# Bubba.net
KiCad netlist of a schematic drawn in EAGLE
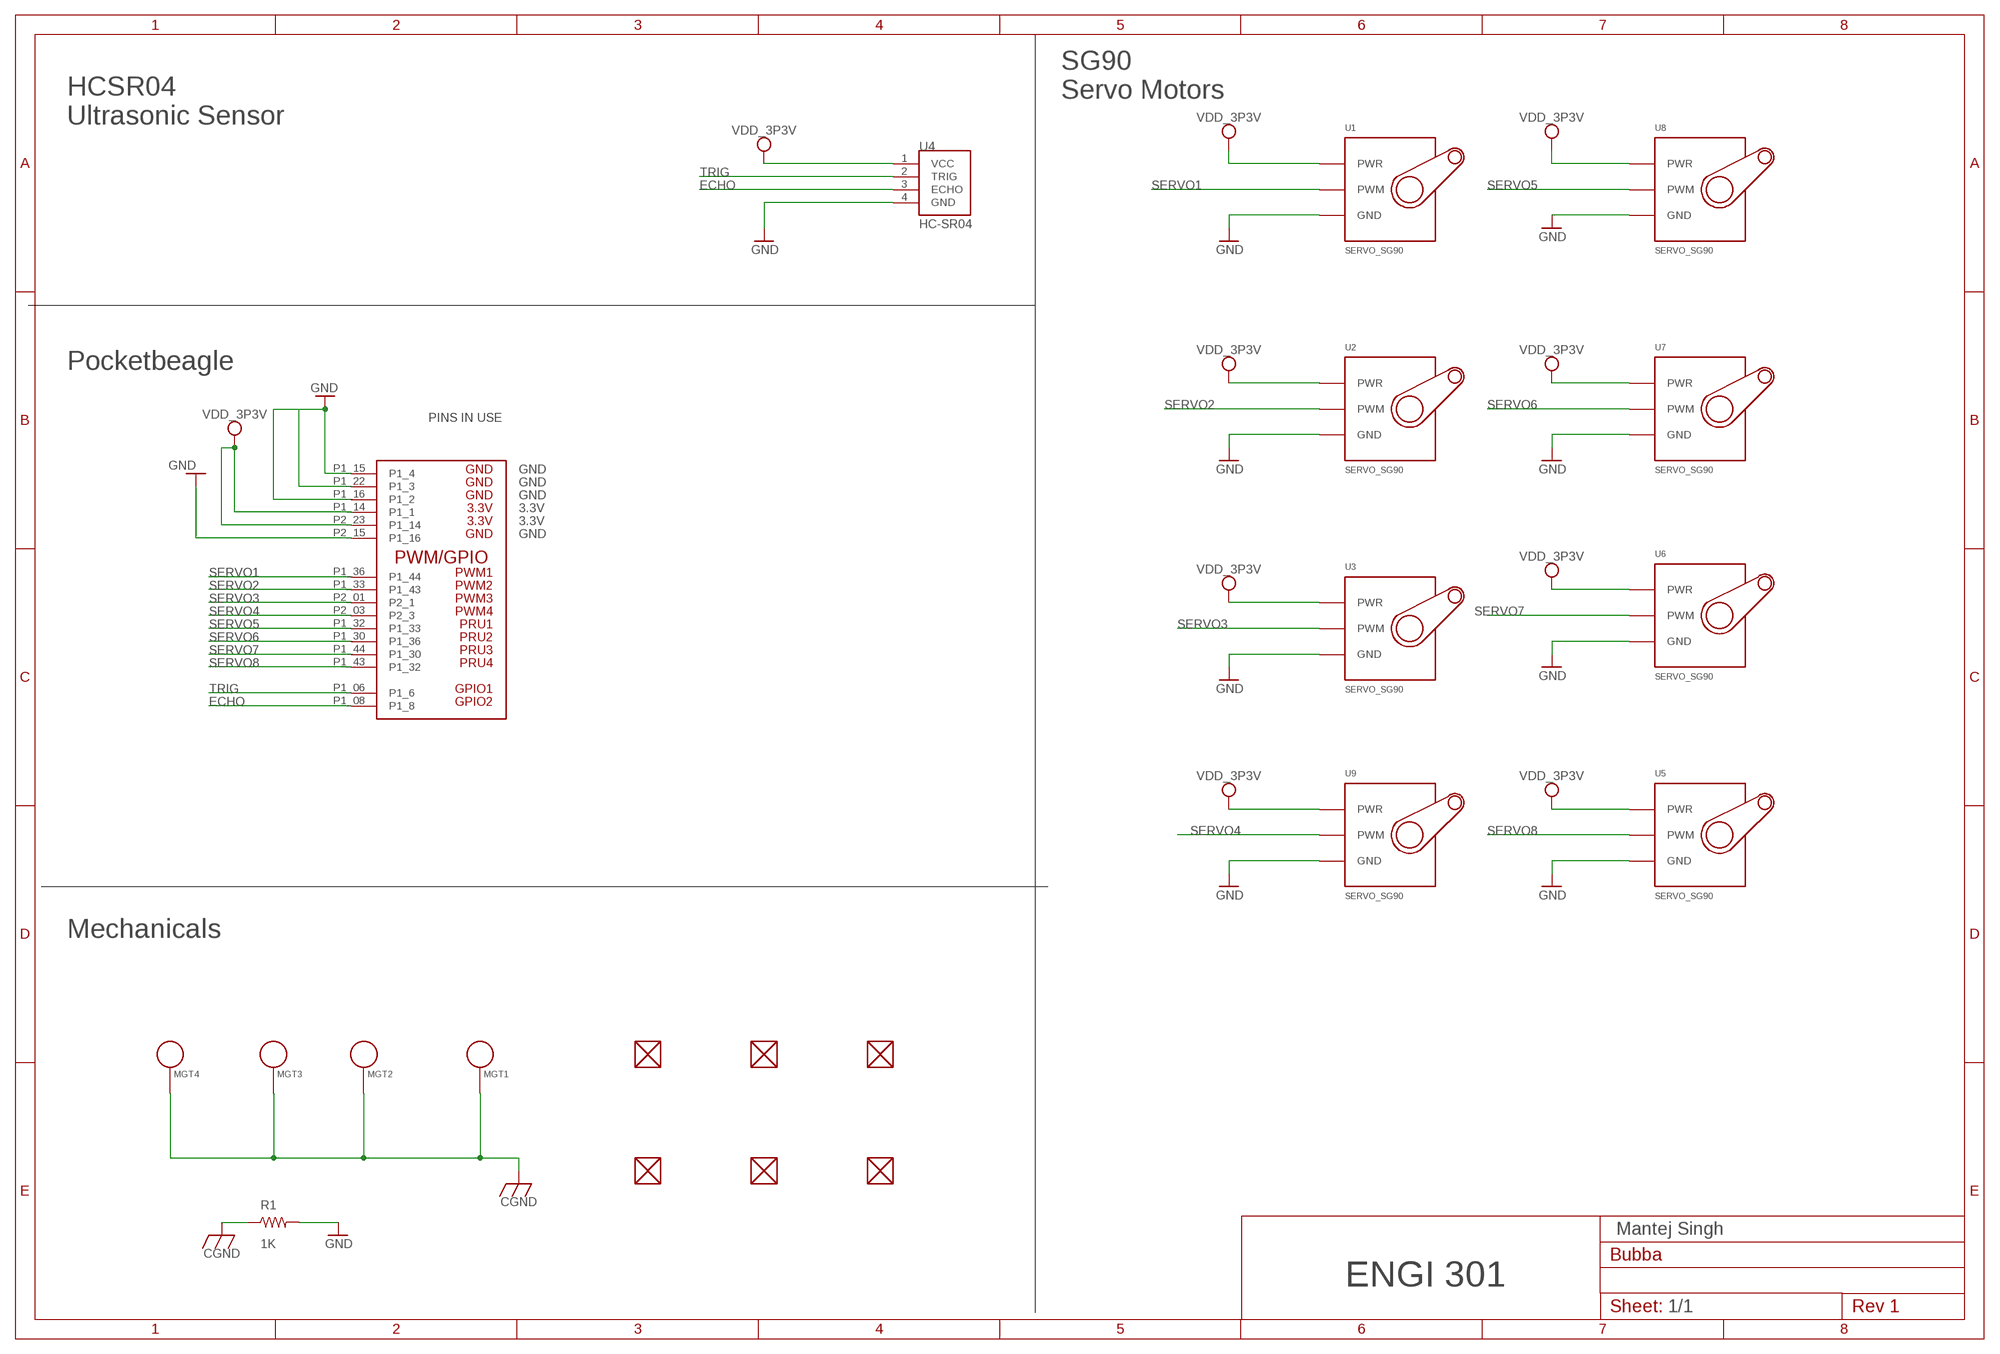
[diagram p0: schematic, sheet 1]

(export (version "E")
  (design (tool "Eeschema 10.0.6"))
  (components
    (comp (ref "FUD1")
      (value "FIDUCIAL")
      (footprint "eagle-import:FIDUCIAL_40MIL")
      (libsource (lib "eagle-import") (part "FIDUCIAL"))
    )
    (comp (ref "FUD2")
      (value "FIDUCIAL")
      (footprint "eagle-import:FIDUCIAL_40MIL")
      (libsource (lib "eagle-import") (part "FIDUCIAL"))
    )
    (comp (ref "FUD3")
      (value "FIDUCIAL")
      (footprint "eagle-import:FIDUCIAL_40MIL")
      (libsource (lib "eagle-import") (part "FIDUCIAL"))
    )
    (comp (ref "FUD4")
      (value "FIDUCIAL")
      (footprint "eagle-import:FIDUCIAL_40MIL")
      (libsource (lib "eagle-import") (part "FIDUCIAL"))
    )
    (comp (ref "FUD5")
      (value "FIDUCIAL")
      (footprint "eagle-import:FIDUCIAL_40MIL")
      (libsource (lib "eagle-import") (part "FIDUCIAL"))
    )
    (comp (ref "FUD6")
      (value "FIDUCIAL")
      (footprint "eagle-import:FIDUCIAL_40MIL")
      (libsource (lib "eagle-import") (part "FIDUCIAL"))
    )
    (comp (ref "MGT1")
      (value "MOUNTING_HOLE")
      (footprint "eagle-import:MOUNTING_HOLE")
      (libsource (lib "eagle-import") (part "MOUNTING_HOLE"))
    )
    (comp (ref "MGT2")
      (value "MOUNTING_HOLE")
      (footprint "eagle-import:MOUNTING_HOLE")
      (libsource (lib "eagle-import") (part "MOUNTING_HOLE"))
    )
    (comp (ref "MGT3")
      (value "MOUNTING_HOLE")
      (footprint "eagle-import:MOUNTING_HOLE")
      (libsource (lib "eagle-import") (part "MOUNTING_HOLE"))
    )
    (comp (ref "MGT4")
      (value "MOUNTING_HOLE")
      (footprint "eagle-import:MOUNTING_HOLE")
      (libsource (lib "eagle-import") (part "MOUNTING_HOLE"))
    )
    (comp (ref "R1")
      (value "1K")
      (footprint "eagle-import:R0805")
      (libsource (lib "eagle-import") (part "R_R0805"))
    )
    (comp (ref "U$1")
      (value "POCKETBEAGLE-MANTEJ")
      (footprint "eagle-import:POCKETBEAGLE-MANTEJ")
      (libsource (lib "eagle-import") (part "POCKETBEAGLE-MANTEJ"))
    )
    (comp (ref "U1")
      (value "SERVO_SG90")
      (footprint "eagle-import:SERVO-X1")
      (libsource (lib "eagle-import") (part "SERVO_SG90"))
    )
    (comp (ref "U2")
      (value "SERVO_SG90")
      (footprint "eagle-import:SERVO-X1")
      (libsource (lib "eagle-import") (part "SERVO_SG90"))
    )
    (comp (ref "U3")
      (value "SERVO_SG90")
      (footprint "eagle-import:SERVO-X1")
      (libsource (lib "eagle-import") (part "SERVO_SG90"))
    )
    (comp (ref "U4")
      (value "HC-SR04")
      (footprint "eagle-import:XCVR_HC-SR04")
      (fields (field (name "MF") "SparkFun Electronics"))
      (libsource (lib "eagle-import") (part "HC-SR04"))
    )
    (comp (ref "U5")
      (value "SERVO_SG90")
      (footprint "eagle-import:SERVO-X1")
      (libsource (lib "eagle-import") (part "SERVO_SG90"))
    )
    (comp (ref "U6")
      (value "SERVO_SG90")
      (footprint "eagle-import:SERVO-X1")
      (libsource (lib "eagle-import") (part "SERVO_SG90"))
    )
    (comp (ref "U7")
      (value "SERVO_SG90")
      (footprint "eagle-import:SERVO-X1")
      (libsource (lib "eagle-import") (part "SERVO_SG90"))
    )
    (comp (ref "U8")
      (value "SERVO_SG90")
      (footprint "eagle-import:SERVO-X1")
      (libsource (lib "eagle-import") (part "SERVO_SG90"))
    )
    (comp (ref "U9")
      (value "SERVO_SG90")
      (footprint "eagle-import:SERVO-X1")
      (libsource (lib "eagle-import") (part "SERVO_SG90"))
    )
  )
  (nets
    (net (code "1") (name "/ECHO") (class "Default")
      (node (ref "U$1") (pin "P1_08") (pinfunction "P1_8_P1_08") (pintype "input"))
      (node (ref "U4") (pin "3") (pinfunction "ECHO_3") (pintype "bidirectional"))
    )
    (net (code "2") (name "/SERVO1") (class "Default")
      (node (ref "U$1") (pin "P1_36") (pinfunction "P1_44_P1_36") (pintype "input"))
      (node (ref "U1") (pin "SIG") (pinfunction "PWM_SIG") (pintype "bidirectional"))
    )
    (net (code "3") (name "/SERVO2") (class "Default")
      (node (ref "U$1") (pin "P1_33") (pinfunction "P1_43_P1_33") (pintype "input"))
      (node (ref "U2") (pin "SIG") (pinfunction "PWM_SIG") (pintype "bidirectional"))
    )
    (net (code "4") (name "/SERVO3") (class "Default")
      (node (ref "U$1") (pin "P2_01") (pinfunction "P2_1_P2_01") (pintype "input"))
      (node (ref "U3") (pin "SIG") (pinfunction "PWM_SIG") (pintype "bidirectional"))
    )
    (net (code "5") (name "/SERVO4") (class "Default")
      (node (ref "U$1") (pin "P2_03") (pinfunction "P2_3_P2_03") (pintype "input"))
      (node (ref "U9") (pin "SIG") (pinfunction "PWM_SIG") (pintype "bidirectional"))
    )
    (net (code "6") (name "/SERVO5") (class "Default")
      (node (ref "U$1") (pin "P1_32") (pinfunction "P1_33_P1_32") (pintype "input"))
      (node (ref "U8") (pin "SIG") (pinfunction "PWM_SIG") (pintype "bidirectional"))
    )
    (net (code "7") (name "/SERVO6") (class "Default")
      (node (ref "U$1") (pin "P1_30") (pinfunction "P1_36_P1_30") (pintype "input"))
      (node (ref "U7") (pin "SIG") (pinfunction "PWM_SIG") (pintype "bidirectional"))
    )
    (net (code "8") (name "/SERVO7") (class "Default")
      (node (ref "U$1") (pin "P1_44") (pinfunction "P1_30_P1_44") (pintype "input"))
      (node (ref "U6") (pin "SIG") (pinfunction "PWM_SIG") (pintype "bidirectional"))
    )
    (net (code "9") (name "/SERVO8") (class "Default")
      (node (ref "U$1") (pin "P1_43") (pinfunction "P1_32_P1_43") (pintype "input"))
      (node (ref "U5") (pin "SIG") (pinfunction "PWM_SIG") (pintype "bidirectional"))
    )
    (net (code "10") (name "/TRIG") (class "Default")
      (node (ref "U$1") (pin "P1_06") (pinfunction "P1_6_P1_06") (pintype "input"))
      (node (ref "U4") (pin "2") (pinfunction "TRIG_2") (pintype "bidirectional"))
    )
    (net (code "11") (name "CGND") (class "Default")
      (node (ref "MGT1") (pin "P$1") (pinfunction "P$1_P$1") (pintype "bidirectional"))
      (node (ref "MGT2") (pin "P$1") (pinfunction "P$1_P$1") (pintype "bidirectional"))
      (node (ref "MGT3") (pin "P$1") (pinfunction "P$1_P$1") (pintype "bidirectional"))
      (node (ref "MGT4") (pin "P$1") (pinfunction "P$1_P$1") (pintype "bidirectional"))
      (node (ref "R1") (pin "1") (pinfunction "1_1") (pintype "passive"))
    )
    (net (code "12") (name "GND") (class "Default")
      (node (ref "R1") (pin "2") (pinfunction "2_2") (pintype "passive"))
      (node (ref "U$1") (pin "P1_15") (pinfunction "P1_4_P1_15") (pintype "bidirectional"))
      (node (ref "U$1") (pin "P1_16") (pinfunction "P1_2_P1_16") (pintype "bidirectional"))
      (node (ref "U$1") (pin "P1_22") (pinfunction "P1_3_P1_22") (pintype "bidirectional"))
      (node (ref "U$1") (pin "P2_15") (pinfunction "P1_16_P2_15") (pintype "bidirectional"))
      (node (ref "U1") (pin "GND") (pinfunction "GND_GND") (pintype "bidirectional"))
      (node (ref "U2") (pin "GND") (pinfunction "GND_GND") (pintype "bidirectional"))
      (node (ref "U3") (pin "GND") (pinfunction "GND_GND") (pintype "bidirectional"))
      (node (ref "U4") (pin "4") (pinfunction "GND_4") (pintype "power_in"))
      (node (ref "U5") (pin "GND") (pinfunction "GND_GND") (pintype "bidirectional"))
      (node (ref "U6") (pin "GND") (pinfunction "GND_GND") (pintype "bidirectional"))
      (node (ref "U7") (pin "GND") (pinfunction "GND_GND") (pintype "bidirectional"))
      (node (ref "U8") (pin "GND") (pinfunction "GND_GND") (pintype "bidirectional"))
      (node (ref "U9") (pin "GND") (pinfunction "GND_GND") (pintype "bidirectional"))
    )
    (net (code "13") (name "VDD_3P3V") (class "Default")
      (node (ref "U$1") (pin "P1_14") (pinfunction "P1_1_P1_14") (pintype "bidirectional"))
      (node (ref "U$1") (pin "P2_23") (pinfunction "P1_14_P2_23") (pintype "bidirectional"))
      (node (ref "U1") (pin "PWR") (pinfunction "PWR_PWR") (pintype "bidirectional"))
      (node (ref "U2") (pin "PWR") (pinfunction "PWR_PWR") (pintype "bidirectional"))
      (node (ref "U3") (pin "PWR") (pinfunction "PWR_PWR") (pintype "bidirectional"))
      (node (ref "U4") (pin "1") (pinfunction "VCC_1") (pintype "power_in"))
      (node (ref "U5") (pin "PWR") (pinfunction "PWR_PWR") (pintype "bidirectional"))
      (node (ref "U6") (pin "PWR") (pinfunction "PWR_PWR") (pintype "bidirectional"))
      (node (ref "U7") (pin "PWR") (pinfunction "PWR_PWR") (pintype "bidirectional"))
      (node (ref "U8") (pin "PWR") (pinfunction "PWR_PWR") (pintype "bidirectional"))
      (node (ref "U9") (pin "PWR") (pinfunction "PWR_PWR") (pintype "bidirectional"))
    )
    (net (code "14") (name "unconnected-(FUD1-PadP$1)") (class "Default")
      (node (ref "FUD1") (pin "P$1") (pinfunction "P$1_P$1") (pintype "no_connect"))
    )
    (net (code "15") (name "unconnected-(FUD2-PadP$1)") (class "Default")
      (node (ref "FUD2") (pin "P$1") (pinfunction "P$1_P$1") (pintype "no_connect"))
    )
    (net (code "16") (name "unconnected-(FUD3-PadP$1)") (class "Default")
      (node (ref "FUD3") (pin "P$1") (pinfunction "P$1_P$1") (pintype "no_connect"))
    )
    (net (code "17") (name "unconnected-(FUD4-PadP$1)") (class "Default")
      (node (ref "FUD4") (pin "P$1") (pinfunction "P$1_P$1") (pintype "no_connect"))
    )
    (net (code "18") (name "unconnected-(FUD5-PadP$1)") (class "Default")
      (node (ref "FUD5") (pin "P$1") (pinfunction "P$1_P$1") (pintype "no_connect"))
    )
    (net (code "19") (name "unconnected-(FUD6-PadP$1)") (class "Default")
      (node (ref "FUD6") (pin "P$1") (pinfunction "P$1_P$1") (pintype "no_connect"))
    )
  )
)
